# 4-CPUMipiXo.net
KiCad netlist of a schematic drawn in Altium Designer
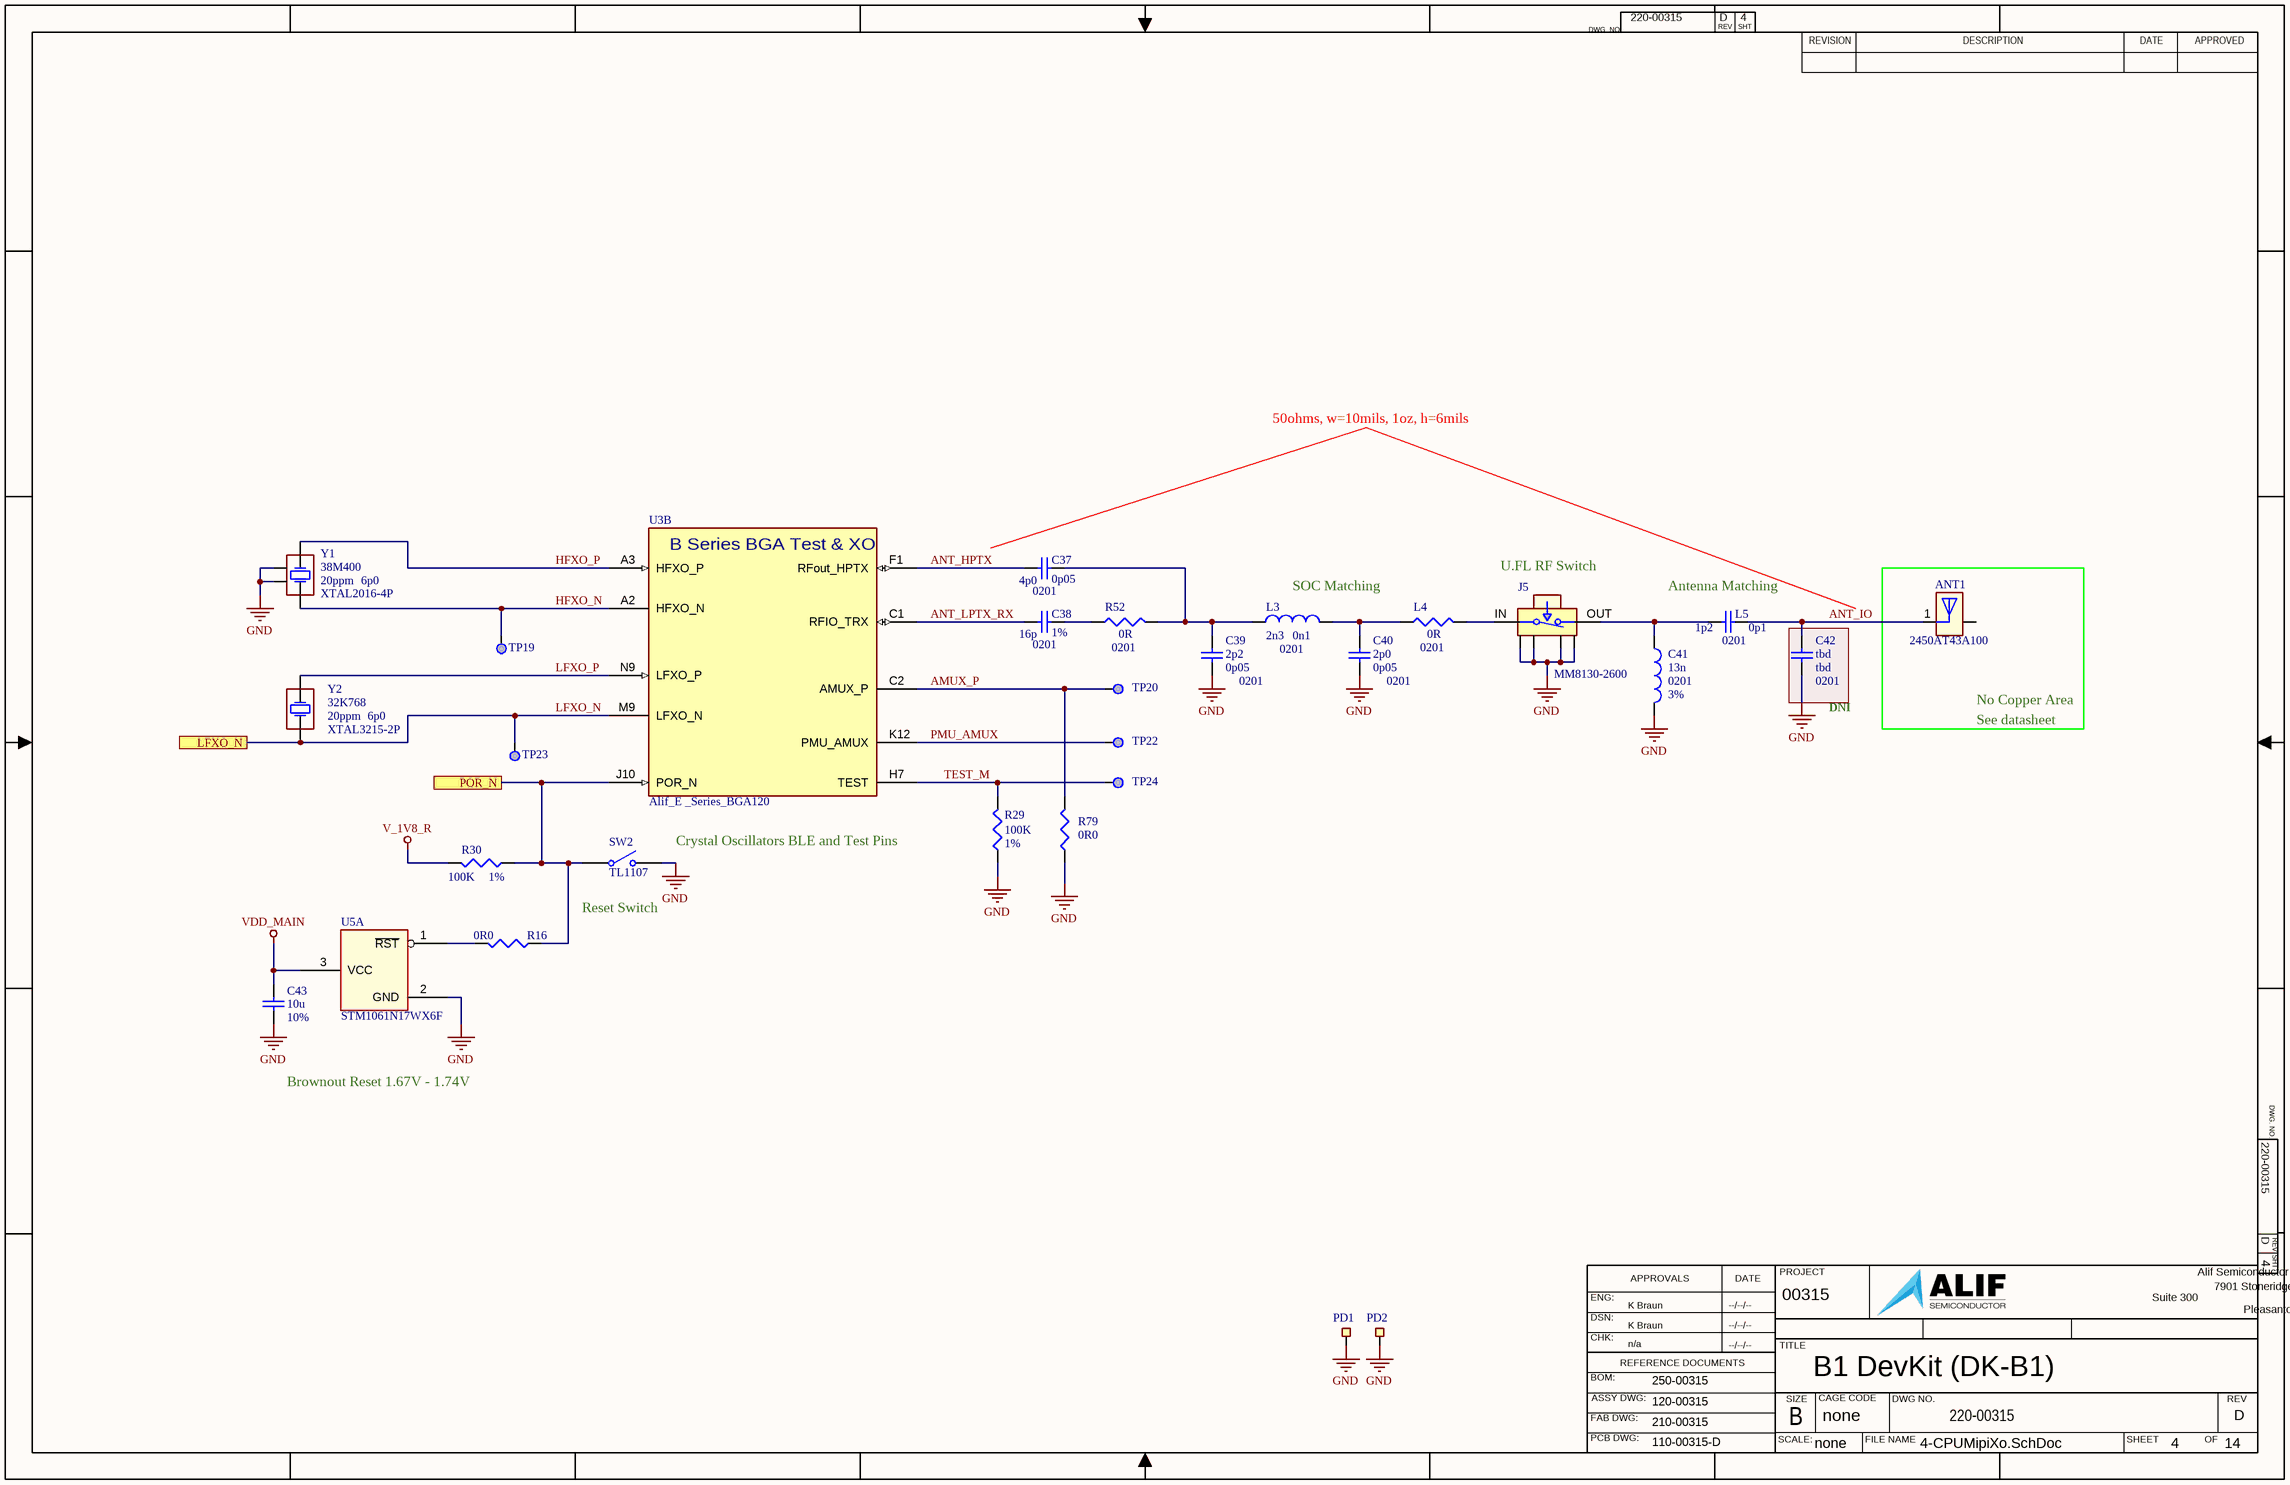
[diagram p0: 4-CPUMipiXo.SchDoc]

(export (version "E")
  (design (tool "Eeschema 10.0.6"))
  (components
    (comp (ref "ANT1")
      (value "2450AT43A100")
      (footprint "ANT_JOT_2450AT43A100_JOD")
      (description "Antenna, Chip, 2.4GHz Bluetooth, ISM, Wi-Fi,  2.7dBi")
      (libsource (lib "Alif-2") (part "ANT_2450AT43A100"))
    )
    (comp (ref "C37")
      (value "4p0")
      (footprint "CC0201_RF10")
      (description "Cap,4.0pF,+-0.05pF,>=25V,C0G,0201")
      (fields
        (field (name "PCB_FOOTPRINT") "0201")
        (field (name "VOLTAGE") "25V")
        (field (name "TOLERANCE") "0p05")
        (field (name "Comment") "Cap")
        (field (name "PUBLISHER") "Altium Limited")
      )
      (libsource (lib "Alif-2") (part "Cap_SMT"))
    )
    (comp (ref "C38")
      (value "16p")
      (footprint "CC0201_RF10")
      (description "Cap,16pF,1%,50V,C0G,0201")
      (fields
        (field (name "PCB_FOOTPRINT") "0201")
        (field (name "VOLTAGE") "25V")
        (field (name "TOLERANCE") "1%")
        (field (name "Comment") "Cap")
        (field (name "PUBLISHER") "Altium Limited")
      )
      (libsource (lib "Alif-2") (part "Cap_SMT"))
    )
    (comp (ref "C39")
      (value "2p2")
      (footprint "CC0201_RF10")
      (description "Cap,2.2pF,+-0.05pF,>25V,C0G,0201")
      (fields
        (field (name "PCB_FOOTPRINT") "0201")
        (field (name "VOLTAGE") "25V")
        (field (name "TOLERANCE") "0p05")
        (field (name "Comment") "Cap")
        (field (name "PUBLISHER") "Altium Limited")
      )
      (libsource (lib "Alif-2") (part "Cap_SMT"))
    )
    (comp (ref "C40")
      (value "2p0")
      (footprint "CC0201_RF10")
      (description "Cap,2.0pF,+-0.05pF,>25V,C0G,0201")
      (fields
        (field (name "PCB_FOOTPRINT") "0201")
        (field (name "VOLTAGE") "25V")
        (field (name "TOLERANCE") "0p05")
        (field (name "Comment") "Cap")
        (field (name "PUBLISHER") "Altium Limited")
      )
      (libsource (lib "Alif-2") (part "Cap_SMT"))
    )
    (comp (ref "C41")
      (value "13n")
      (footprint "LC0201_RF10")
      (description "Ind,13nH,+-3%,>300mA,ESR < 800mOhm,SRF >4.3GHz,Q >12 @ 500MHz,0201")
      (fields
        (field (name "PCB_FOOTPRINT") "0201")
        (field (name "TOLERANCE") "3%")
        (field (name "Comment") "Inductor")
        (field (name "PUBLISHER") "Altium Limited")
      )
      (libsource (lib "Alif-2") (part "Inductor"))
    )
    (comp (ref "C42")
      (value "tbd")
      (footprint "CC0201_RF10")
      (description "DNI,Cap,tbd,tbd,>25V,C0G,0201")
      (fields
        (field (name "PCB_FOOTPRINT") "0201")
        (field (name "VOLTAGE") "25V")
        (field (name "TOLERANCE") "tbd")
        (field (name "Comment") "Cap")
        (field (name "PUBLISHER") "Altium Limited")
      )
      (libsource (lib "Alif-2") (part "Cap_SMT"))
    )
    (comp (ref "C43")
      (value "10u")
      (footprint "CAPC0402-01")
      (description "Cap,10uF,20%,10V,X5R,0402")
      (fields
        (field (name "VOLTAGE") "10V")
        (field (name "TOLERANCE") "10%")
        (field (name "Comment") "Cap")
        (field (name "PUBLISHER") "Altium Limited")
      )
      (libsource (lib "kb1") (part "Cap"))
    )
    (comp (ref "J5")
      (value "MM8130-2600")
      (footprint "CONN_U.FL_SWITCH_MURATA_MM8130-2600RA2")
      (description "Conn,U.FL, Switch, Male Pin 50Ohm 6-Pin SMT")
      (libsource (lib "Alif-2") (part "CONN_U.FL_SWITCH_MM8130-2600"))
    )
    (comp (ref "L3")
      (value "2n3")
      (footprint "LC0201_RF10")
      (description "Ind,2.3nH,+-0.1nH,>500mA,ESR < 250mOhm,SRF >7GHz,Q >20 @ 500MHz,0201")
      (fields
        (field (name "PCB_FOOTPRINT") "0201")
        (field (name "TOLERANCE") "0n1")
        (field (name "Comment") "Inductor")
        (field (name "PUBLISHER") "Altium Limited")
      )
      (libsource (lib "Alif-2") (part "Inductor"))
    )
    (comp (ref "L4")
      (value "0R")
      (footprint "RC0201_RF10")
      (description "Res,0R ohm,Jumper,0201")
      (fields
        (field (name "PCB_FOOTPRINT") "0201")
        (field (name "TOLERANCE") "1%")
        (field (name "Comment") "Res3")
        (field (name "PUBLISHER") "Altium Limited")
      )
      (libsource (lib "Alif-2") (part "Res3"))
    )
    (comp (ref "L5")
      (value "1p2")
      (footprint "CC0201_RF10")
      (description "Cap,1.2pF,<+-0.10pF,25-50V,C0G,0201")
      (fields
        (field (name "PCB_FOOTPRINT") "0201")
        (field (name "VOLTAGE") "50V")
        (field (name "TOLERANCE") "0p1")
        (field (name "Comment") "Cap")
        (field (name "PUBLISHER") "Altium Limited")
      )
      (libsource (lib "Alif-2") (part "Cap_SMT"))
    )
    (comp (ref "PD1")
      (value "PAD_10x10")
      (footprint "PAD_RF10x10")
      (description "Test Point, SMT Pad,--not a BOM item--")
      (libsource (lib "Alif2") (part "PAD_0101"))
    )
    (comp (ref "PD2")
      (value "PAD_10x10")
      (footprint "PAD_RF10x10")
      (description "Test Point, SMT Pad,--not a BOM item--")
      (libsource (lib "Alif2") (part "PAD_0101"))
    )
    (comp (ref "R16")
      (value "0R0")
      (footprint "RESC0402-01")
      (description "Res,0R ohm,Jumper,0402")
      (fields
        (field (name "TOLERANCE") "JMPR")
        (field (name "Comment") "Res3")
        (field (name "PUBLISHER") "Altium Limited")
      )
      (libsource (lib "kb1") (part "Res3"))
    )
    (comp (ref "R29")
      (value "100K")
      (footprint "RESC0402-01")
      (description "Res,100K,1%,100ppm,0402")
      (fields
        (field (name "TOLERANCE") "1%")
        (field (name "Comment") "Res3")
        (field (name "PUBLISHER") "Altium Limited")
      )
      (libsource (lib "kb1") (part "Res3"))
    )
    (comp (ref "R30")
      (value "100K")
      (footprint "RESC0402-01")
      (description "Res,100K,1%,100ppm,0402")
      (fields
        (field (name "TOLERANCE") "1%")
        (field (name "Comment") "Res3")
        (field (name "PUBLISHER") "Altium Limited")
      )
      (libsource (lib "kb1") (part "Res3"))
    )
    (comp (ref "R52")
      (value "0R")
      (footprint "RC0201_RF10")
      (description "Res,0R ohm,Jumper,0201")
      (fields
        (field (name "PCB_FOOTPRINT") "0201")
        (field (name "TOLERANCE") "1%")
        (field (name "Comment") "Res3")
        (field (name "PUBLISHER") "Altium Limited")
      )
      (libsource (lib "Alif-2") (part "Res3"))
    )
    (comp (ref "R79")
      (value "0R0")
      (footprint "RESC0402-01")
      (description "Res,0R ohm,Jumper,0402")
      (fields
        (field (name "TOLERANCE") "JMPR")
        (field (name "Comment") "Res3")
        (field (name "PUBLISHER") "Altium Limited")
      )
      (libsource (lib "kb1") (part "Res3"))
    )
    (comp (ref "SW2")
      (value "TL1107")
      (footprint "SW_1825966-TL1107-1")
      (description "Swit, SPST, Momentary Pushputton, 2 pin, 6.0x3.5mm, H=5.0mm")
      (fields (field (name "Comment") "SW-SPST") (field (name "PUBLISHER") "Altium Limited"))
      (libsource (lib "Alif-2") (part "SW-SPST"))
    )
    (comp (ref "TP19")
      (value "TP_SMPAD")
      (footprint "TP_30_RND")
      (description "Test Point, SMT Pad,--not a BOM item--")
      (libsource (lib "Alif-2") (part "TP_SMPAD"))
    )
    (comp (ref "TP20")
      (value "TP_SMPAD")
      (footprint "TP_30_RND")
      (description "Test Point, SMT Pad,--not a BOM item--")
      (libsource (lib "Alif-2") (part "TP_SMPAD"))
    )
    (comp (ref "TP22")
      (value "TP_SMPAD")
      (footprint "TP_30_RND")
      (description "Test Point, SMT Pad,--not a BOM item--")
      (libsource (lib "Alif-2") (part "TP_SMPAD"))
    )
    (comp (ref "TP23")
      (value "TP_SMPAD")
      (footprint "TP_30_RND")
      (description "Test Point, SMT Pad,--not a BOM item--")
      (libsource (lib "Alif-2") (part "TP_SMPAD"))
    )
    (comp (ref "TP24")
      (value "TP_SMPAD")
      (footprint "TP_30_RND")
      (description "Test Point, SMT Pad,--not a BOM item--")
      (libsource (lib "Alif-2") (part "TP_SMPAD"))
    )
    (comp (ref "U3")
      (value "Alif_E _Series_BGA120")
      (footprint "BGA120_socket-NO_SOCK_3D")
      (description "IC,Alif Spark B1 MCU, Rev A5 silicon,BGA120")
      (libsource (lib "Alif") (part "SPARK_B1_120BGA_A5"))
    )
    (comp (ref "U5")
      (value "STM1061N17WX6F")
      (footprint "SOT-23_DBZ_TEX")
      (description "IC,PMIC Volt Supervisor, -Reset OD, 1.7V, 2%, 900nA, SOT23-3")
      (libsource (lib "Alif-2") (part "IC_SUP_STM1061N17WX6F"))
    )
    (comp (ref "Y1")
      (value "38M400")
      (footprint "OSC_4p_2016_XRCGB38M400F2P00R0")
      (description "Crystal,38.4MHz,20ppm,6.0pF,100ohm,2016-4pin")
      (fields
        (field (name "PCB_FOOTPRINT") "XTAL2016-4P")
        (field (name "PPM") "20ppm")
        (field (name "LOAD CAP") "6p0")
        (field (name "Comment") "Xtal_38M4_20PPM6PF_2016-4P_1")
        (field (name "PUBLISHER") "Altium Limited")
      )
      (libsource (lib "Alif-2") (part "Xtal_38M4_20PPM6PF_2016-4P_1"))
    )
    (comp (ref "Y2")
      (value "32K768")
      (footprint "XTAL_ABS07_ABR-M")
      (description "Crystal, 32.768KHz, 20ppm, 6pF, <70Kohm, 3215-2pin")
      (fields
        (field (name "PCB_FOOTPRINT") "XTAL3215-2P")
        (field (name "PPM") "20ppm")
        (field (name "LOAD CAP") "6p0")
        (field (name "Comment") "Xtal_32K768_20PPM6PF_3215-2P_1")
        (field (name "PUBLISHER") "Altium Limited")
      )
      (libsource (lib "Alif-2") (part "Xtal_32K768_20PPM6PF_3215-2P_1"))
    )
  )
  (nets
    (net (code "1") (name "/AMUX_P") (class "Default")
      (node (ref "R79") (pin "2") (pinfunction "2_2") (pintype "passive"))
      (node (ref "TP20") (pin "1") (pinfunction "1_1") (pintype "passive"))
      (node (ref "U3") (pin "C2") (pinfunction "AMUX_P_C2") (pintype "passive"))
    )
    (net (code "2") (name "/ANT_HPTX") (class "Default")
      (node (ref "C37") (pin "2") (pinfunction "2_2") (pintype "passive"))
      (node (ref "U3") (pin "F1") (pinfunction "RFout_HPTX_F1") (pintype "bidirectional"))
    )
    (net (code "3") (name "/ANT_IO") (class "Default")
      (node (ref "ANT1") (pin "1") (pinfunction "INPUT_1") (pintype "passive"))
      (node (ref "C42") (pin "2") (pinfunction "2_2") (pintype "passive"))
      (node (ref "L5") (pin "1") (pinfunction "1_1") (pintype "passive"))
    )
    (net (code "4") (name "/ANT_LPTX_RX") (class "Default")
      (node (ref "C38") (pin "2") (pinfunction "2_2") (pintype "passive"))
      (node (ref "U3") (pin "C1") (pinfunction "RFIO_TRX_C1") (pintype "bidirectional"))
    )
    (net (code "5") (name "/HFXO_N") (class "Default")
      (node (ref "TP19") (pin "1") (pinfunction "1_1") (pintype "passive"))
      (node (ref "U3") (pin "A2") (pinfunction "HFXO_N_A2") (pintype "passive"))
      (node (ref "Y1") (pin "3") (pinfunction "OSC2_3") (pintype "passive"))
    )
    (net (code "6") (name "/HFXO_P") (class "Default")
      (node (ref "U3") (pin "A3") (pinfunction "HFXO_P_A3") (pintype "input"))
      (node (ref "Y1") (pin "1") (pinfunction "OSC1_1") (pintype "passive"))
    )
    (net (code "7") (name "/LFXO_N") (class "Default")
      (node (ref "TP23") (pin "1") (pinfunction "1_1") (pintype "passive"))
      (node (ref "U3") (pin "M9") (pinfunction "LFXO_N_M9") (pintype "passive"))
      (node (ref "Y2") (pin "1") (pinfunction "OSC1_1") (pintype "passive"))
    )
    (net (code "8") (name "/LFXO_P") (class "Default")
      (node (ref "U3") (pin "N9") (pinfunction "LFXO_P_N9") (pintype "input"))
      (node (ref "Y2") (pin "2") (pinfunction "OSC2_2") (pintype "passive"))
    )
    (net (code "9") (name "/PMU_AMUX") (class "Default")
      (node (ref "TP22") (pin "1") (pinfunction "1_1") (pintype "passive"))
      (node (ref "U3") (pin "K12") (pinfunction "PMU_AMUX_K12") (pintype "passive"))
    )
    (net (code "10") (name "/POR_N") (class "Default")
      (node (ref "R16") (pin "1") (pinfunction "1_1") (pintype "passive"))
      (node (ref "R30") (pin "1") (pinfunction "1_1") (pintype "passive"))
      (node (ref "SW2") (pin "1") (pinfunction "COMMON_1") (pintype "passive"))
      (node (ref "U3") (pin "J10") (pinfunction "POR_N_J10") (pintype "input"))
    )
    (net (code "11") (name "/TEST_M") (class "Default")
      (node (ref "R29") (pin "2") (pinfunction "2_2") (pintype "passive"))
      (node (ref "TP24") (pin "1") (pinfunction "1_1") (pintype "passive"))
      (node (ref "U3") (pin "H7") (pinfunction "TEST_H7") (pintype "passive"))
    )
    (net (code "12") (name "GND") (class "Default")
      (node (ref "C39") (pin "1") (pinfunction "1_1") (pintype "passive"))
      (node (ref "C40") (pin "1") (pinfunction "1_1") (pintype "passive"))
      (node (ref "C41") (pin "2") (pinfunction "2_2") (pintype "passive"))
      (node (ref "C42") (pin "1") (pinfunction "1_1") (pintype "passive"))
      (node (ref "C43") (pin "1") (pinfunction "1_1") (pintype "passive"))
      (node (ref "J5") (pin "G1") (pinfunction "G1_G1") (pintype "passive"))
      (node (ref "J5") (pin "G2") (pinfunction "G2_G2") (pintype "passive"))
      (node (ref "J5") (pin "G3") (pinfunction "G3_G3") (pintype "passive"))
      (node (ref "J5") (pin "G4") (pinfunction "G4_G4") (pintype "passive"))
      (node (ref "PD1") (pin "1") (pinfunction "1_1") (pintype "passive"))
      (node (ref "PD2") (pin "1") (pinfunction "1_1") (pintype "passive"))
      (node (ref "R29") (pin "1") (pinfunction "1_1") (pintype "passive"))
      (node (ref "R79") (pin "1") (pinfunction "1_1") (pintype "passive"))
      (node (ref "SW2") (pin "2") (pinfunction "NO_2") (pintype "passive"))
      (node (ref "U5") (pin "2") (pinfunction "GND_2") (pintype "power_in"))
      (node (ref "Y1") (pin "2") (pinfunction "2_2") (pintype "passive"))
      (node (ref "Y1") (pin "4") (pinfunction "4_4") (pintype "passive"))
    )
    (net (code "13") (name "Net-(C37-Pad1)") (class "Default")
      (node (ref "C37") (pin "1") (pinfunction "1_1") (pintype "passive"))
      (node (ref "C39") (pin "2") (pinfunction "2_2") (pintype "passive"))
      (node (ref "L3") (pin "1") (pinfunction "1_1") (pintype "passive"))
      (node (ref "R52") (pin "2") (pinfunction "2_2") (pintype "passive"))
    )
    (net (code "14") (name "Net-(C38-Pad1)") (class "Default")
      (node (ref "C38") (pin "1") (pinfunction "1_1") (pintype "passive"))
      (node (ref "R52") (pin "1") (pinfunction "1_1") (pintype "passive"))
    )
    (net (code "15") (name "Net-(C40-Pad2)") (class "Default")
      (node (ref "C40") (pin "2") (pinfunction "2_2") (pintype "passive"))
      (node (ref "L3") (pin "2") (pinfunction "2_2") (pintype "passive"))
      (node (ref "L4") (pin "1") (pinfunction "1_1") (pintype "passive"))
    )
    (net (code "16") (name "Net-(C41-Pad1)") (class "Default")
      (node (ref "C41") (pin "1") (pinfunction "1_1") (pintype "passive"))
      (node (ref "J5") (pin "OUT") (pinfunction "OUT_OUT") (pintype "passive"))
      (node (ref "L5") (pin "2") (pinfunction "2_2") (pintype "passive"))
    )
    (net (code "17") (name "Net-(J5-PadIN)") (class "Default")
      (node (ref "J5") (pin "IN") (pinfunction "IN_IN") (pintype "passive"))
      (node (ref "L4") (pin "2") (pinfunction "2_2") (pintype "passive"))
    )
    (net (code "18") (name "Net-(U5-~{RST})") (class "Default")
      (node (ref "R16") (pin "2") (pinfunction "2_2") (pintype "passive"))
      (node (ref "U5") (pin "1") (pinfunction "~{RST}_1") (pintype "open_collector"))
    )
    (net (code "19") (name "VDD_MAIN") (class "Default")
      (node (ref "C43") (pin "2") (pinfunction "2_2") (pintype "passive"))
      (node (ref "U5") (pin "3") (pinfunction "VCC_3") (pintype "power_in"))
    )
    (net (code "20") (name "V_1V8_R") (class "Default")
      (node (ref "R30") (pin "2") (pinfunction "2_2") (pintype "passive"))
    )
    (net (code "21") (name "unconnected-(ANT1-GND-Pad3)") (class "Default")
      (node (ref "ANT1") (pin "3") (pinfunction "GND_3") (pintype "power_in"))
    )
  )
)
